# com.net
KiCad netlist of a schematic drawn in Altium Designer
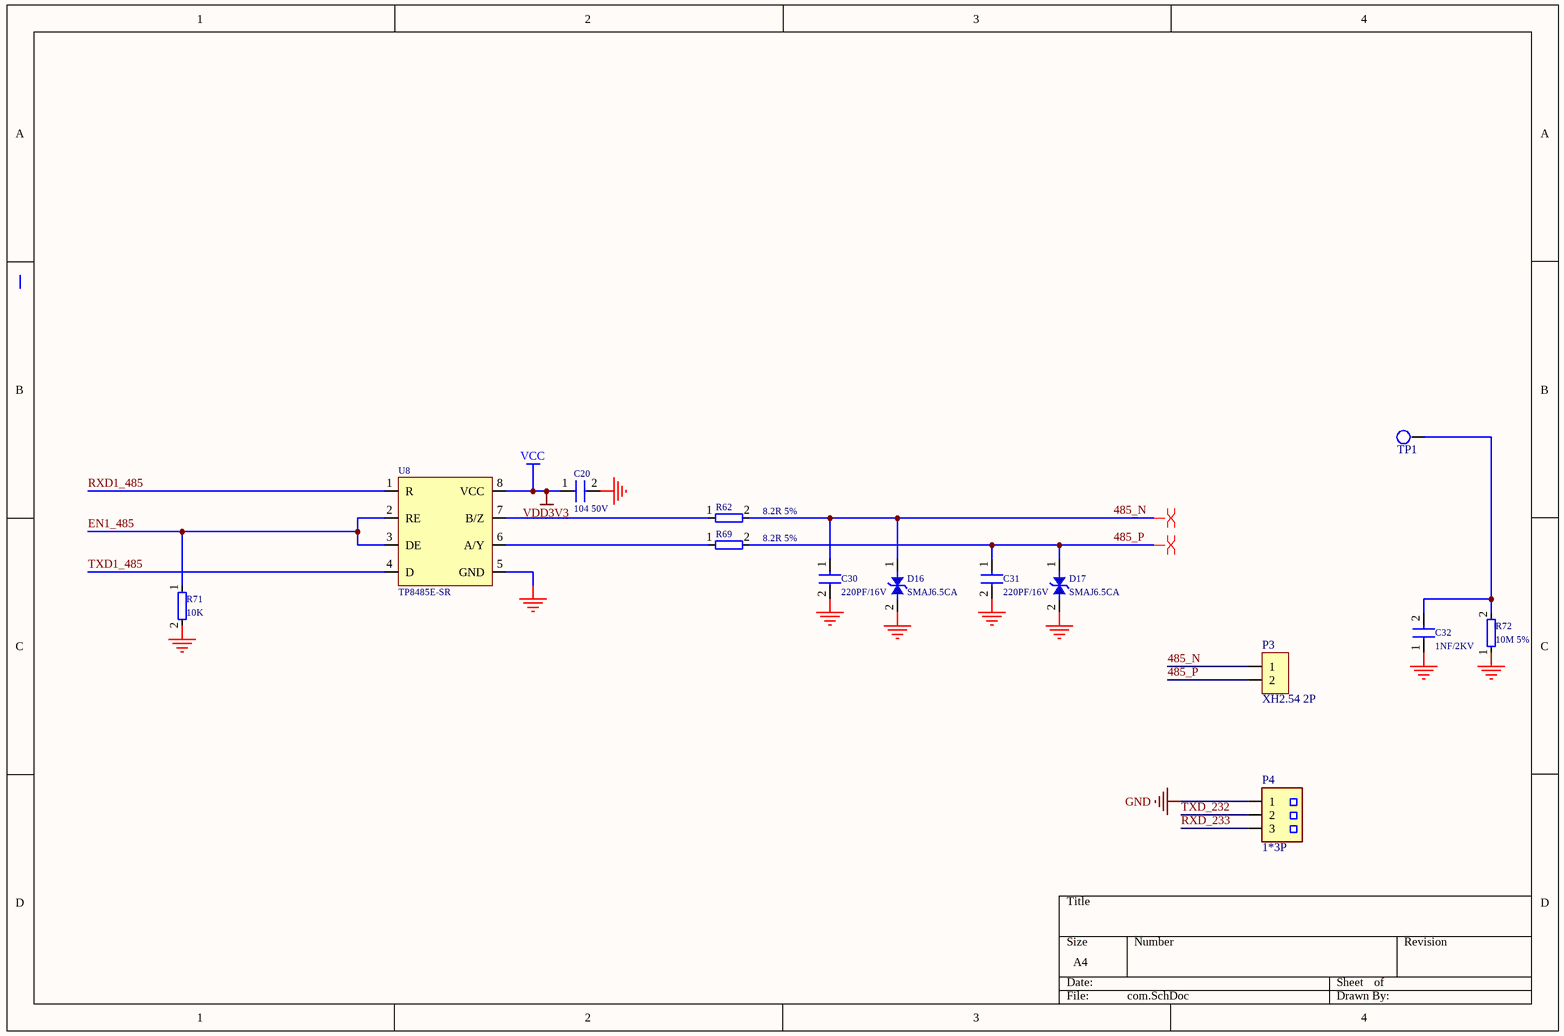
[diagram p0: com.SchDoc]

(export (version "E")
  (design (tool "Eeschema 10.0.6"))
  (components
    (comp (ref "C20") (value "104 50V") (footprint "0603C") (libsource (lib "*") (part "CAP")))
    (comp (ref "C30") (value "220PF/16V") (footprint "0603C") (libsource (lib "*") (part "CAP")))
    (comp (ref "C31") (value "220PF/16V") (footprint "0603C") (libsource (lib "*") (part "CAP")))
    (comp (ref "C32") (value "1NF/2KV") (footprint "1206C") (libsource (lib "*") (part "CAP")))
    (comp (ref "D16") (value "SMAJ6.5CA") (footprint "SMA") (libsource (lib "*") (part "D_ESD")))
    (comp (ref "D17") (value "SMAJ6.5CA") (footprint "SMA") (libsource (lib "*") (part "D_ESD")))
    (comp (ref "P3")
      (value "XH2.54 2P")
      (footprint "SIP-2A")
      (description "XH2.54 2P 直插")
      (libsource (lib "XiaoyI") (part "SIP-2"))
    )
    (comp (ref "P4") (value "1*3P") (footprint "3X2.54MMZ2") (libsource (lib "PARK-N5 V1.0") (part "HDR1*3")))
    (comp (ref "R62") (value "8.2R 5%") (footprint "0603R") (libsource (lib "*") (part "RES")))
    (comp (ref "R69") (value "8.2R 5%") (footprint "0603R") (libsource (lib "*") (part "RES")))
    (comp (ref "R71") (value "10K") (footprint "0603R") (libsource (lib "*") (part "RES")))
    (comp (ref "R72") (value "10M 5%") (footprint "1206r") (libsource (lib "*") (part "RES")))
    (comp (ref "TP1") (value "TPS") (footprint "tpd") (libsource (lib "stm32") (part "TPS")))
    (comp (ref "U8") (value "TP8485E-SR") (footprint "SO-8") (libsource (lib "*") (part "TP8485E-SR")))
  )
  (nets
    (net (code "1") (name "/485_N") (class "Default")
      (node (ref "C30") (pin "1") (pintype "passive"))
      (node (ref "D16") (pin "1") (pintype "passive"))
      (node (ref "P3") (pin "1") (pinfunction "1_1") (pintype "passive"))
      (node (ref "R62") (pin "2") (pinfunction "2_2") (pintype "passive"))
    )
    (net (code "2") (name "/485_P") (class "Default")
      (node (ref "C31") (pin "1") (pintype "passive"))
      (node (ref "D17") (pin "1") (pintype "passive"))
      (node (ref "P3") (pin "2") (pinfunction "2_2") (pintype "passive"))
      (node (ref "R69") (pin "2") (pinfunction "2_2") (pintype "passive"))
    )
    (net (code "3") (name "/EN1_485") (class "Default")
      (node (ref "R71") (pin "1") (pinfunction "1_1") (pintype "passive"))
      (node (ref "U8") (pin "2") (pinfunction "RE_2") (pintype "passive"))
      (node (ref "U8") (pin "3") (pinfunction "DE_3") (pintype "passive"))
    )
    (net (code "4") (name "/RXD1_485") (class "Default")
      (node (ref "U8") (pin "1") (pinfunction "R_1") (pintype "passive"))
    )
    (net (code "5") (name "/RXD_233") (class "Default")
      (node (ref "P4") (pin "3") (pinfunction "3_3") (pintype "passive"))
    )
    (net (code "6") (name "/TXD1_485") (class "Default")
      (node (ref "U8") (pin "4") (pinfunction "D_4") (pintype "passive"))
    )
    (net (code "7") (name "/TXD_232") (class "Default")
      (node (ref "P4") (pin "2") (pinfunction "2_2") (pintype "passive"))
    )
    (net (code "8") (name "GND") (class "Default")
      (node (ref "C20") (pin "2") (pintype "passive"))
      (node (ref "C30") (pin "2") (pintype "passive"))
      (node (ref "C31") (pin "2") (pintype "passive"))
      (node (ref "C32") (pin "1") (pintype "passive"))
      (node (ref "D16") (pin "2") (pintype "passive"))
      (node (ref "D17") (pin "2") (pintype "passive"))
      (node (ref "P4") (pin "1") (pinfunction "1_1") (pintype "passive"))
      (node (ref "R71") (pin "2") (pinfunction "2_2") (pintype "passive"))
      (node (ref "R72") (pin "1") (pinfunction "1_1") (pintype "passive"))
      (node (ref "U8") (pin "5") (pinfunction "GND_5") (pintype "passive"))
    )
    (net (code "9") (name "Net-(C32-Pad2)") (class "Default")
      (node (ref "C32") (pin "2") (pintype "passive"))
      (node (ref "R72") (pin "2") (pinfunction "2_2") (pintype "passive"))
      (node (ref "TP1") (pin "1") (pinfunction "1_1") (pintype "passive"))
    )
    (net (code "10") (name "Net-(U8-A{slash}Y)") (class "Default")
      (node (ref "R69") (pin "1") (pinfunction "1_1") (pintype "passive"))
      (node (ref "U8") (pin "6") (pinfunction "A/Y_6") (pintype "passive"))
    )
    (net (code "11") (name "Net-(U8-B{slash}Z)") (class "Default")
      (node (ref "R62") (pin "1") (pinfunction "1_1") (pintype "passive"))
      (node (ref "U8") (pin "7") (pinfunction "B/Z_7") (pintype "passive"))
    )
    (net (code "12") (name "VCC") (class "Default")
      (node (ref "C20") (pin "1") (pintype "passive"))
      (node (ref "U8") (pin "8") (pinfunction "VCC_8") (pintype "passive"))
    )
  )
)
